# External_SDRAM.net
KiCad netlist of a schematic drawn in Altium Designer
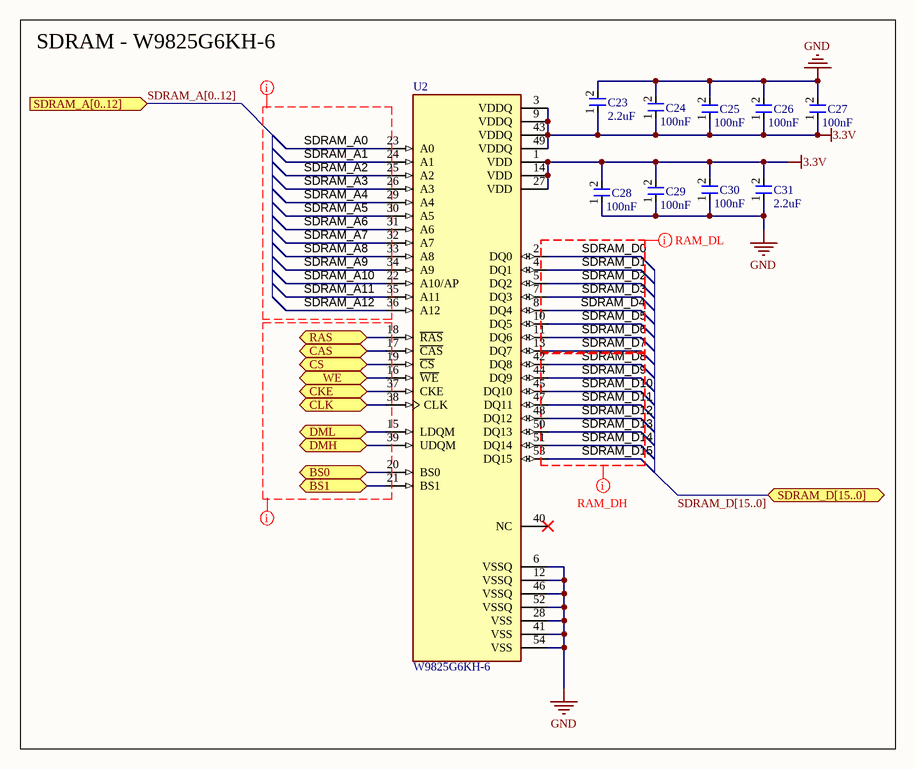
[diagram p0: External SDRAM.SchDoc]

(export (version "E")
  (design (tool "Eeschema 10.0.6"))
  (components
    (comp (ref "C23")
      (value "0603")
      (footprint "0603 Cap")
      (fields (field (name "C") "2.2uF"))
      (libsource (lib "VoltaRoket") (part "0603 Cap"))
    )
    (comp (ref "C24")
      (value "0603")
      (footprint "0603 Cap")
      (fields (field (name "C") "100nF"))
      (libsource (lib "VoltaRoket") (part "0603 Cap"))
    )
    (comp (ref "C25")
      (value "0603")
      (footprint "0603 Cap")
      (fields (field (name "C") "100nF"))
      (libsource (lib "VoltaRoket") (part "0603 Cap"))
    )
    (comp (ref "C26")
      (value "0603")
      (footprint "0603 Cap")
      (fields (field (name "C") "100nF"))
      (libsource (lib "VoltaRoket") (part "0603 Cap"))
    )
    (comp (ref "C27")
      (value "0603")
      (footprint "0603 Cap")
      (fields (field (name "C") "100nF"))
      (libsource (lib "VoltaRoket") (part "0603 Cap"))
    )
    (comp (ref "C28")
      (value "0603")
      (footprint "0603 Cap")
      (fields (field (name "C") "100nF"))
      (libsource (lib "VoltaRoket") (part "0603 Cap"))
    )
    (comp (ref "C29")
      (value "0603")
      (footprint "0603 Cap")
      (fields (field (name "C") "100nF"))
      (libsource (lib "VoltaRoket") (part "0603 Cap"))
    )
    (comp (ref "C30")
      (value "0603")
      (footprint "0603 Cap")
      (fields (field (name "C") "100nF"))
      (libsource (lib "VoltaRoket") (part "0603 Cap"))
    )
    (comp (ref "C31")
      (value "0603")
      (footprint "0603 Cap")
      (fields (field (name "C") "2.2uF"))
      (libsource (lib "VoltaRoket") (part "0603 Cap"))
    )
    (comp (ref "U2")
      (value "W9825G6KH-6")
      (footprint "SOP80P1176X120-54N")
      (description "SDRAM Memory IC 256Mb (16M x 16) Parallel 166MHz 5ns 54-TSOP II")
      (fields (field (name "MF") "{'manufacturer': u'Winbond Electronics'}"))
      (libsource (lib "W9825G6KH-6") (part "W9825G6KH-6"))
    )
  )
  (nets
    (net (code "1") (name "/BS0") (class "Default")
      (node (ref "U2") (pin "20") (pinfunction "BS0_20") (pintype "input"))
    )
    (net (code "2") (name "/BS1") (class "Default")
      (node (ref "U2") (pin "21") (pinfunction "BS1_21") (pintype "input"))
    )
    (net (code "3") (name "/CAS") (class "Default")
      (node (ref "U2") (pin "17") (pinfunction "~{CAS}_17") (pintype "input"))
    )
    (net (code "4") (name "/CKE") (class "Default")
      (node (ref "U2") (pin "37") (pinfunction "CKE_37") (pintype "input"))
    )
    (net (code "5") (name "/CLK") (class "Default")
      (node (ref "U2") (pin "38") (pinfunction "CLK_38") (pintype "input"))
    )
    (net (code "6") (name "/CS") (class "Default")
      (node (ref "U2") (pin "19") (pinfunction "~{CS}_19") (pintype "input"))
    )
    (net (code "7") (name "/DMH") (class "Default")
      (node (ref "U2") (pin "39") (pinfunction "UDQM_39") (pintype "input"))
    )
    (net (code "8") (name "/DML") (class "Default")
      (node (ref "U2") (pin "15") (pinfunction "LDQM_15") (pintype "input"))
    )
    (net (code "9") (name "/RAS") (class "Default")
      (node (ref "U2") (pin "18") (pinfunction "~{RAS}_18") (pintype "input"))
    )
    (net (code "10") (name "/SDRAM_A0") (class "Default")
      (node (ref "U2") (pin "23") (pinfunction "A0_23") (pintype "input"))
    )
    (net (code "11") (name "/SDRAM_A1") (class "Default")
      (node (ref "U2") (pin "24") (pinfunction "A1_24") (pintype "input"))
    )
    (net (code "12") (name "/SDRAM_A2") (class "Default")
      (node (ref "U2") (pin "25") (pinfunction "A2_25") (pintype "input"))
    )
    (net (code "13") (name "/SDRAM_A3") (class "Default")
      (node (ref "U2") (pin "26") (pinfunction "A3_26") (pintype "input"))
    )
    (net (code "14") (name "/SDRAM_A4") (class "Default")
      (node (ref "U2") (pin "29") (pinfunction "A4_29") (pintype "input"))
    )
    (net (code "15") (name "/SDRAM_A5") (class "Default")
      (node (ref "U2") (pin "30") (pinfunction "A5_30") (pintype "input"))
    )
    (net (code "16") (name "/SDRAM_A6") (class "Default")
      (node (ref "U2") (pin "31") (pinfunction "A6_31") (pintype "input"))
    )
    (net (code "17") (name "/SDRAM_A7") (class "Default")
      (node (ref "U2") (pin "32") (pinfunction "A7_32") (pintype "input"))
    )
    (net (code "18") (name "/SDRAM_A8") (class "Default")
      (node (ref "U2") (pin "33") (pinfunction "A8_33") (pintype "input"))
    )
    (net (code "19") (name "/SDRAM_A9") (class "Default")
      (node (ref "U2") (pin "34") (pinfunction "A9_34") (pintype "input"))
    )
    (net (code "20") (name "/SDRAM_A10") (class "Default")
      (node (ref "U2") (pin "22") (pinfunction "A10/AP_22") (pintype "input"))
    )
    (net (code "21") (name "/SDRAM_A11") (class "Default")
      (node (ref "U2") (pin "35") (pinfunction "A11_35") (pintype "input"))
    )
    (net (code "22") (name "/SDRAM_A12") (class "Default")
      (node (ref "U2") (pin "36") (pinfunction "A12_36") (pintype "input"))
    )
    (net (code "24") (name "/SDRAM_D0") (class "Default")
      (node (ref "U2") (pin "2") (pinfunction "DQ0_2") (pintype "bidirectional"))
    )
    (net (code "25") (name "/SDRAM_D1") (class "Default")
      (node (ref "U2") (pin "4") (pinfunction "DQ1_4") (pintype "bidirectional"))
    )
    (net (code "26") (name "/SDRAM_D2") (class "Default")
      (node (ref "U2") (pin "5") (pinfunction "DQ2_5") (pintype "bidirectional"))
    )
    (net (code "27") (name "/SDRAM_D3") (class "Default")
      (node (ref "U2") (pin "7") (pinfunction "DQ3_7") (pintype "bidirectional"))
    )
    (net (code "28") (name "/SDRAM_D4") (class "Default")
      (node (ref "U2") (pin "8") (pinfunction "DQ4_8") (pintype "bidirectional"))
    )
    (net (code "29") (name "/SDRAM_D5") (class "Default")
      (node (ref "U2") (pin "10") (pinfunction "DQ5_10") (pintype "bidirectional"))
    )
    (net (code "30") (name "/SDRAM_D6") (class "Default")
      (node (ref "U2") (pin "11") (pinfunction "DQ6_11") (pintype "bidirectional"))
    )
    (net (code "31") (name "/SDRAM_D7") (class "Default")
      (node (ref "U2") (pin "13") (pinfunction "DQ7_13") (pintype "bidirectional"))
    )
    (net (code "32") (name "/SDRAM_D8") (class "Default")
      (node (ref "U2") (pin "42") (pinfunction "DQ8_42") (pintype "bidirectional"))
    )
    (net (code "33") (name "/SDRAM_D9") (class "Default")
      (node (ref "U2") (pin "44") (pinfunction "DQ9_44") (pintype "bidirectional"))
    )
    (net (code "34") (name "/SDRAM_D10") (class "Default")
      (node (ref "U2") (pin "45") (pinfunction "DQ10_45") (pintype "bidirectional"))
    )
    (net (code "35") (name "/SDRAM_D11") (class "Default")
      (node (ref "U2") (pin "47") (pinfunction "DQ11_47") (pintype "bidirectional"))
    )
    (net (code "36") (name "/SDRAM_D12") (class "Default")
      (node (ref "U2") (pin "48") (pinfunction "DQ12_48") (pintype "bidirectional"))
    )
    (net (code "37") (name "/SDRAM_D13") (class "Default")
      (node (ref "U2") (pin "50") (pinfunction "DQ13_50") (pintype "bidirectional"))
    )
    (net (code "38") (name "/SDRAM_D14") (class "Default")
      (node (ref "U2") (pin "51") (pinfunction "DQ14_51") (pintype "bidirectional"))
    )
    (net (code "39") (name "/SDRAM_D15") (class "Default")
      (node (ref "U2") (pin "53") (pinfunction "DQ15_53") (pintype "bidirectional"))
    )
    (net (code "41") (name "/WE") (class "Default")
      (node (ref "U2") (pin "16") (pinfunction "~{WE}_16") (pintype "input"))
    )
    (net (code "42") (name "3.3V") (class "Default")
      (node (ref "C23") (pin "1") (pinfunction "1_1") (pintype "passive"))
      (node (ref "C24") (pin "1") (pinfunction "1_1") (pintype "passive"))
      (node (ref "C25") (pin "1") (pinfunction "1_1") (pintype "passive"))
      (node (ref "C26") (pin "1") (pinfunction "1_1") (pintype "passive"))
      (node (ref "C27") (pin "1") (pinfunction "1_1") (pintype "passive"))
      (node (ref "C28") (pin "2") (pinfunction "2_2") (pintype "passive"))
      (node (ref "C29") (pin "2") (pinfunction "2_2") (pintype "passive"))
      (node (ref "C30") (pin "2") (pinfunction "2_2") (pintype "passive"))
      (node (ref "C31") (pin "2") (pinfunction "2_2") (pintype "passive"))
      (node (ref "U2") (pin "1") (pinfunction "VDD_1") (pintype "power_in"))
      (node (ref "U2") (pin "14") (pinfunction "VDD_14") (pintype "power_in"))
      (node (ref "U2") (pin "27") (pinfunction "VDD_27") (pintype "power_in"))
      (node (ref "U2") (pin "3") (pinfunction "VDDQ_3") (pintype "power_in"))
      (node (ref "U2") (pin "43") (pinfunction "VDDQ_43") (pintype "power_in"))
      (node (ref "U2") (pin "49") (pinfunction "VDDQ_49") (pintype "power_in"))
      (node (ref "U2") (pin "9") (pinfunction "VDDQ_9") (pintype "power_in"))
    )
    (net (code "43") (name "GND") (class "Default")
      (node (ref "C23") (pin "2") (pinfunction "2_2") (pintype "passive"))
      (node (ref "C24") (pin "2") (pinfunction "2_2") (pintype "passive"))
      (node (ref "C25") (pin "2") (pinfunction "2_2") (pintype "passive"))
      (node (ref "C26") (pin "2") (pinfunction "2_2") (pintype "passive"))
      (node (ref "C27") (pin "2") (pinfunction "2_2") (pintype "passive"))
      (node (ref "C28") (pin "1") (pinfunction "1_1") (pintype "passive"))
      (node (ref "C29") (pin "1") (pinfunction "1_1") (pintype "passive"))
      (node (ref "C30") (pin "1") (pinfunction "1_1") (pintype "passive"))
      (node (ref "C31") (pin "1") (pinfunction "1_1") (pintype "passive"))
      (node (ref "U2") (pin "12") (pinfunction "VSSQ_12") (pintype "power_in"))
      (node (ref "U2") (pin "28") (pinfunction "VSS_28") (pintype "power_in"))
      (node (ref "U2") (pin "41") (pinfunction "VSS_41") (pintype "power_in"))
      (node (ref "U2") (pin "46") (pinfunction "VSSQ_46") (pintype "power_in"))
      (node (ref "U2") (pin "52") (pinfunction "VSSQ_52") (pintype "power_in"))
      (node (ref "U2") (pin "54") (pinfunction "VSS_54") (pintype "power_in"))
      (node (ref "U2") (pin "6") (pinfunction "VSSQ_6") (pintype "power_in"))
    )
    (net (code "44") (name "unconnected-(U2-NC-Pad40)") (class "Default")
      (node (ref "U2") (pin "40") (pinfunction "NC_40") (pintype "passive+no_connect"))
    )
  )
)
